# DS_NEW.net
KiCad netlist of a schematic drawn in Altium Designer
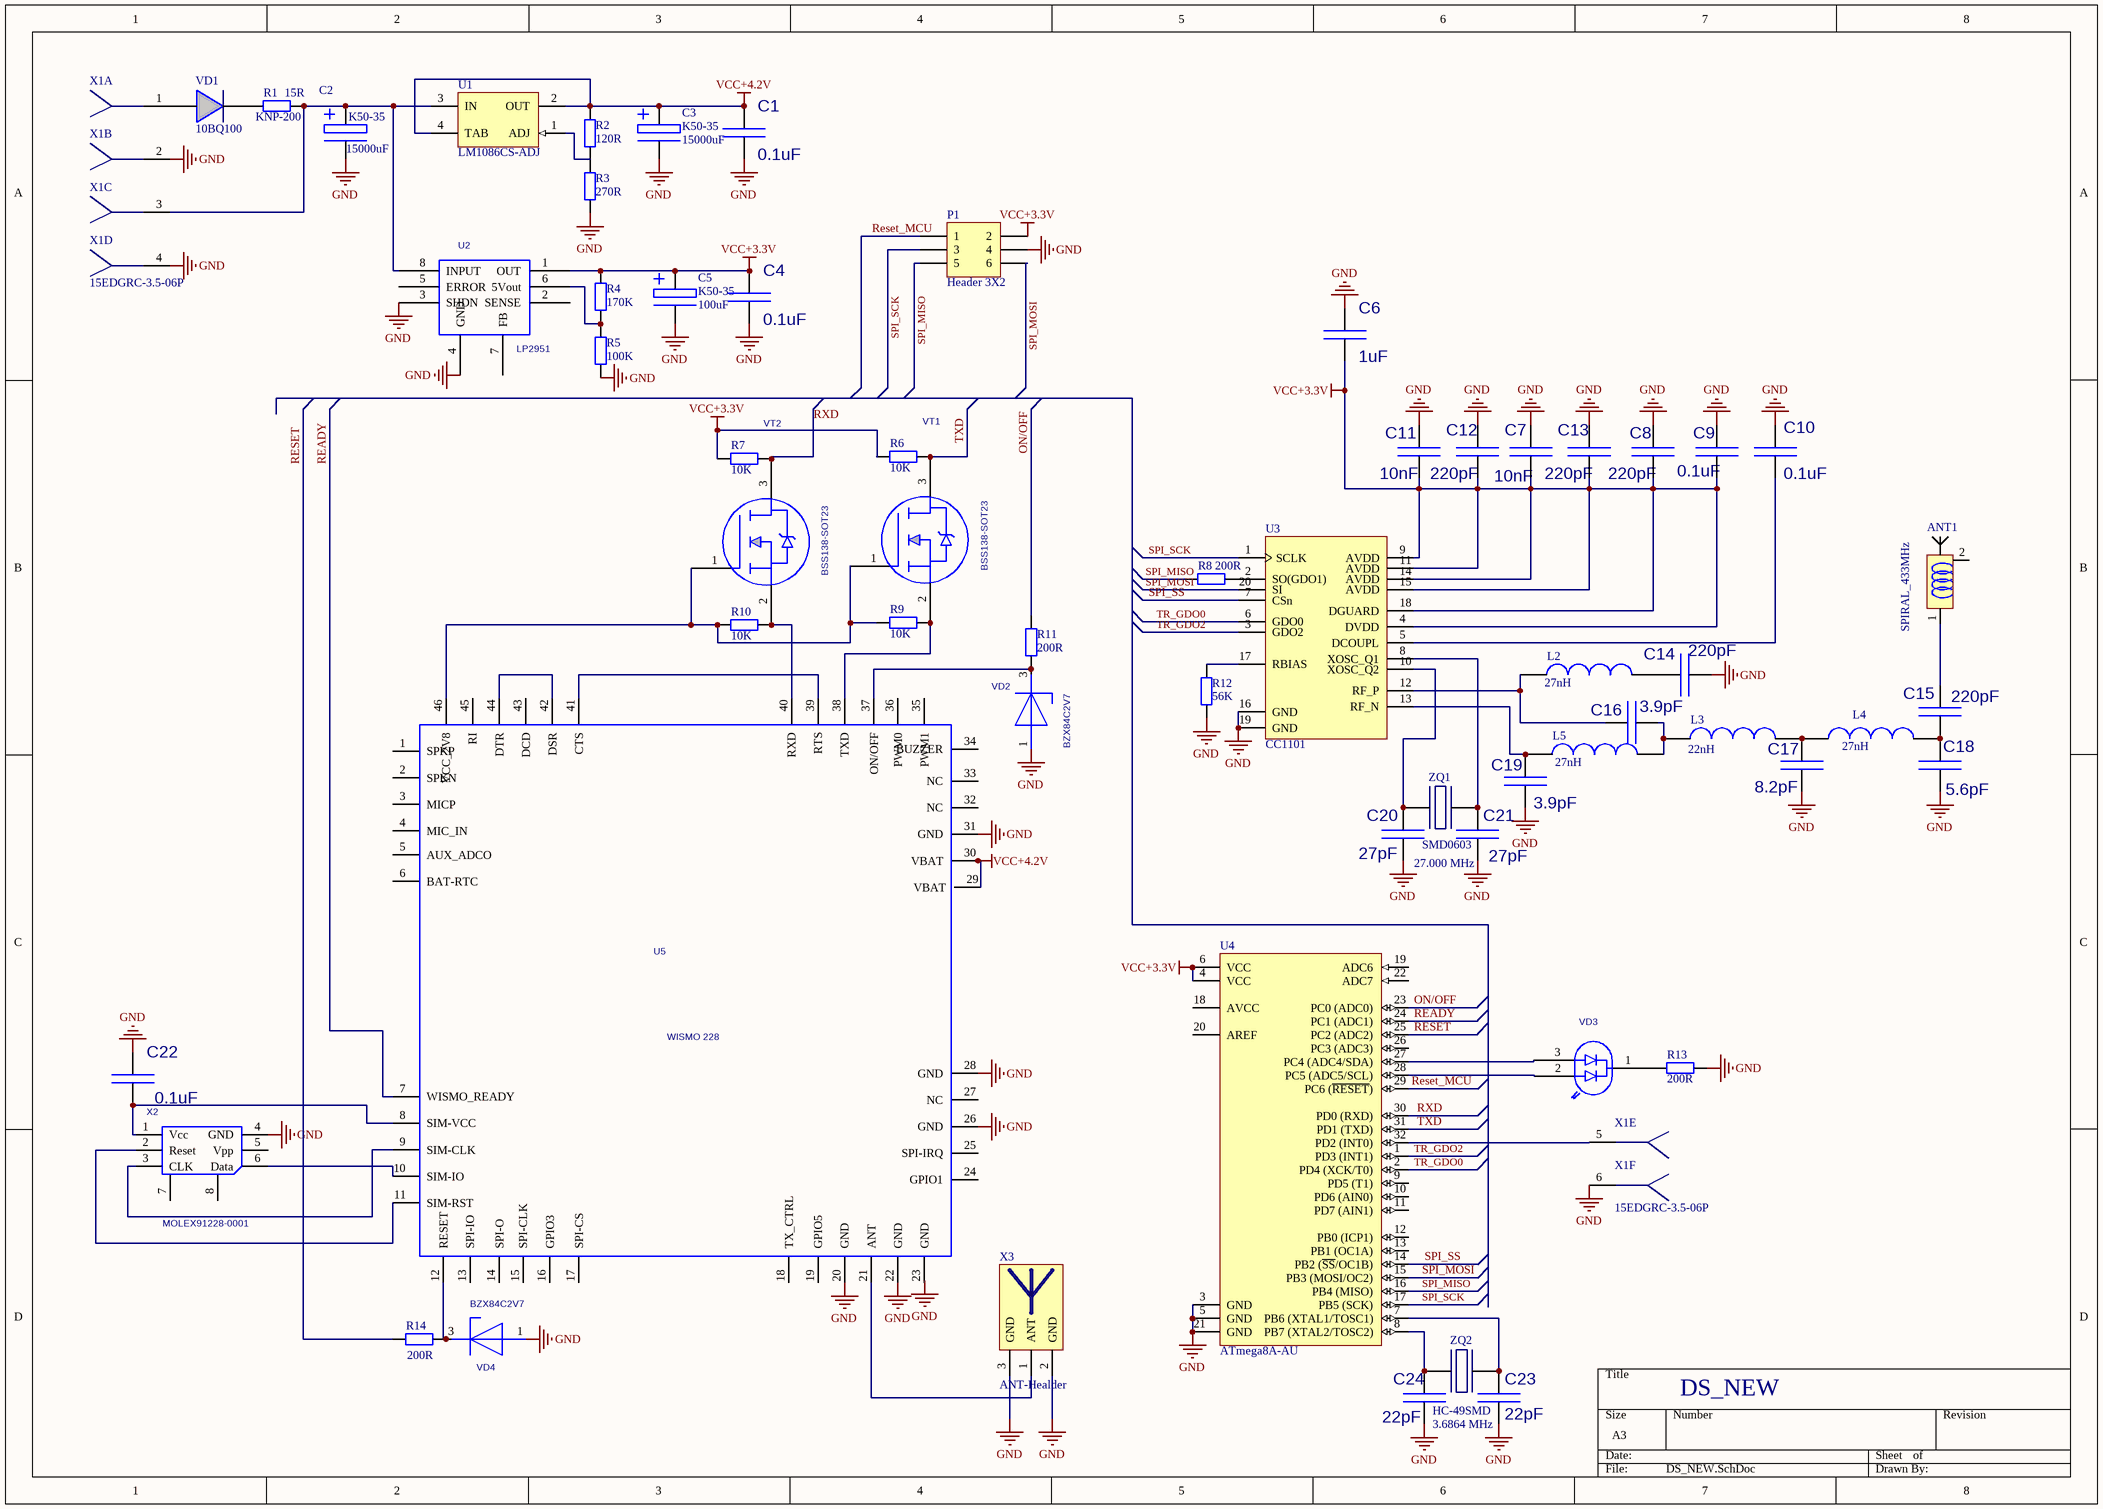
[diagram p0: DS_NEW.SchDoc]

(export (version "E")
  (design (tool "Eeschema 10.0.6"))
  (components
    (comp (ref "ANT1")
      (value "SPIRAL_433MHz")
      (footprint "ANT_433MHz_SPIRAL")
      (libsource (lib "NEW") (part "ANT_433MHz_SPIRAL"))
    )
    (comp (ref "C1")
      (value "0.1uF")
      (footprint "C0805")
      (description "KONDENS_SMD")
      (libsource (lib "NEW") (part "KONDENS_SMD"))
    )
    (comp (ref "C2")
      (value "K50-35")
      (footprint "CAP_POL_D18-Horizontal")
      (fields (field (name "ALTIUM_UNNAMED_1") "15000uF"))
      (libsource (lib "NEW") (part "Capasitor _pol D18"))
    )
    (comp (ref "C3")
      (value "K50-35")
      (footprint "CAP_POL_D18-Horizontal")
      (fields (field (name "ALTIUM_UNNAMED_1") "15000uF"))
      (libsource (lib "NEW") (part "Capasitor _pol D18"))
    )
    (comp (ref "C4")
      (value "0.1uF")
      (footprint "C0805")
      (description "KONDENS_SMD")
      (libsource (lib "NEW") (part "KONDENS_SMD"))
    )
    (comp (ref "C5")
      (value "K50-35")
      (footprint "CAP_POL_D6.3")
      (fields (field (name "ALTIUM_VALUE") "100uF"))
      (libsource (lib "NEW") (part "Capasitor_pol D6.3"))
    )
    (comp (ref "C6")
      (value "1uF")
      (footprint "C0805")
      (description "KONDENS_SMD")
      (libsource (lib "NEW") (part "KONDENS_SMD"))
    )
    (comp (ref "C7")
      (value "10nF")
      (footprint "C0805")
      (description "KONDENS_SMD")
      (libsource (lib "NEW") (part "KONDENS_SMD"))
    )
    (comp (ref "C8")
      (value "220pF")
      (footprint "C0805")
      (description "KONDENS_SMD")
      (libsource (lib "NEW") (part "KONDENS_SMD"))
    )
    (comp (ref "C9")
      (value "0.1uF")
      (footprint "C0805")
      (description "KONDENS_SMD")
      (libsource (lib "NEW") (part "KONDENS_SMD"))
    )
    (comp (ref "C10")
      (value "0.1uF")
      (footprint "C0805")
      (description "KONDENS_SMD")
      (libsource (lib "NEW") (part "KONDENS_SMD"))
    )
    (comp (ref "C11")
      (value "10nF")
      (footprint "C0805")
      (description "KONDENS_SMD")
      (libsource (lib "NEW") (part "KONDENS_SMD"))
    )
    (comp (ref "C12")
      (value "220pF")
      (footprint "C0805")
      (description "KONDENS_SMD")
      (libsource (lib "NEW") (part "KONDENS_SMD"))
    )
    (comp (ref "C13")
      (value "220pF")
      (footprint "C0805")
      (description "KONDENS_SMD")
      (libsource (lib "NEW") (part "KONDENS_SMD"))
    )
    (comp (ref "C14")
      (value "220pF")
      (footprint "C0805")
      (description "KONDENS_SMD")
      (libsource (lib "NEW") (part "KONDENS_SMD"))
    )
    (comp (ref "C15")
      (value "220pF")
      (footprint "C0805")
      (description "KONDENS_SMD")
      (libsource (lib "NEW") (part "KONDENS_SMD"))
    )
    (comp (ref "C16")
      (value "3.9pF")
      (footprint "C0805")
      (description "KONDENS_SMD")
      (libsource (lib "NEW") (part "KONDENS_SMD"))
    )
    (comp (ref "C17")
      (value "8.2pF")
      (footprint "C0805")
      (description "KONDENS_SMD")
      (libsource (lib "NEW") (part "KONDENS_SMD"))
    )
    (comp (ref "C18")
      (value "5.6pF")
      (footprint "C0805")
      (description "KONDENS_SMD")
      (libsource (lib "NEW") (part "KONDENS_SMD"))
    )
    (comp (ref "C19")
      (value "3.9pF")
      (footprint "C0805")
      (description "KONDENS_SMD")
      (libsource (lib "NEW") (part "KONDENS_SMD"))
    )
    (comp (ref "C20")
      (value "27pF")
      (footprint "C0805")
      (description "KONDENS_SMD")
      (libsource (lib "NEW") (part "KONDENS_SMD"))
    )
    (comp (ref "C21")
      (value "27pF")
      (footprint "C0805")
      (description "KONDENS_SMD")
      (libsource (lib "NEW") (part "KONDENS_SMD"))
    )
    (comp (ref "C22")
      (value "0.1uF")
      (footprint "C0805")
      (description "KONDENS_SMD")
      (libsource (lib "NEW") (part "KONDENS_SMD"))
    )
    (comp (ref "C23")
      (value "22pF")
      (footprint "C0805")
      (description "KONDENS_SMD")
      (libsource (lib "NEW") (part "KONDENS_SMD"))
    )
    (comp (ref "C24")
      (value "22pF")
      (footprint "C0805")
      (description "KONDENS_SMD")
      (libsource (lib "NEW") (part "KONDENS_SMD"))
    )
    (comp (ref "L2")
      (value "27nH")
      (footprint "6-0805_M")
      (fields (field (name "Comment") "SMD_0805"))
      (libsource (lib "NEW") (part "Induktor_0805"))
    )
    (comp (ref "L3")
      (value "22nH")
      (footprint "6-0805_M")
      (fields (field (name "Comment") "SMD_0805"))
      (libsource (lib "NEW") (part "Induktor_0805"))
    )
    (comp (ref "L4")
      (value "27nH")
      (footprint "6-0805_M")
      (fields (field (name "Comment") "SMD_0805"))
      (libsource (lib "NEW") (part "Induktor_0805"))
    )
    (comp (ref "L5")
      (value "27nH")
      (footprint "6-0805_M")
      (fields (field (name "Comment") "SMD_0805"))
      (libsource (lib "NEW") (part "Induktor_0805"))
    )
    (comp (ref "P1")
      (value "Header 3X2")
      (footprint "HDR2X3")
      (description "Header, 3-Pin, Dual row")
      (fields (field (name "PUBLISHER") "Altium Limited"))
      (libsource (lib "Miscellaneous Connectors") (part "Header 3X2"))
    )
    (comp (ref "R1")
      (value "KNP-200")
      (footprint "Resistor KNP-200")
      (fields (field (name "ALTIUM_UNNAMED_1") "15R"))
      (libsource (lib "NEW") (part "Resistor 2W"))
    )
    (comp (ref "R2")
      (value "120R")
      (footprint "C0805")
      (description "Resistor")
      (fields (field (name "Comment") "RES"))
      (libsource (lib "") (part "RES_1"))
    )
    (comp (ref "R3")
      (value "270R")
      (footprint "C0805")
      (description "Resistor")
      (fields (field (name "Comment") "RES"))
      (libsource (lib "") (part "RES_1"))
    )
    (comp (ref "R4")
      (value "170K")
      (footprint "C0805")
      (description "Resistor")
      (fields (field (name "Comment") "RES"))
      (libsource (lib "") (part "RES_1"))
    )
    (comp (ref "R5")
      (value "100K")
      (footprint "C0805")
      (description "Resistor")
      (fields (field (name "Comment") "RES"))
      (libsource (lib "") (part "RES_1"))
    )
    (comp (ref "R6")
      (value "10K")
      (footprint "C0805")
      (description "Resistor")
      (fields (field (name "Comment") "RES"))
      (libsource (lib "NEW") (part "RES"))
    )
    (comp (ref "R7")
      (value "10K")
      (footprint "C0805")
      (description "Resistor")
      (fields (field (name "Comment") "RES"))
      (libsource (lib "NEW") (part "RES"))
    )
    (comp (ref "R8")
      (value "200R")
      (footprint "C0805")
      (description "Resistor")
      (fields (field (name "Comment") "RES"))
      (libsource (lib "NEW") (part "RES"))
    )
    (comp (ref "R9")
      (value "10K")
      (footprint "C0805")
      (description "Resistor")
      (fields (field (name "Comment") "RES"))
      (libsource (lib "NEW") (part "RES"))
    )
    (comp (ref "R10")
      (value "10K")
      (footprint "C0805")
      (description "Resistor")
      (fields (field (name "Comment") "RES"))
      (libsource (lib "NEW") (part "RES"))
    )
    (comp (ref "R11")
      (value "200R")
      (footprint "C0805")
      (description "Resistor")
      (fields (field (name "Comment") "RES"))
      (libsource (lib "") (part "RES_1"))
    )
    (comp (ref "R12")
      (value "56K")
      (footprint "C0805")
      (description "Resistor")
      (fields (field (name "Comment") "RES"))
      (libsource (lib "") (part "RES_1"))
    )
    (comp (ref "R13")
      (value "200R")
      (footprint "C0805")
      (description "Resistor")
      (fields (field (name "Comment") "RES"))
      (libsource (lib "NEW") (part "RES"))
    )
    (comp (ref "R14")
      (value "200R")
      (footprint "C0805")
      (description "Resistor")
      (fields (field (name "Comment") "RES"))
      (libsource (lib "NEW") (part "RES"))
    )
    (comp (ref "U1")
      (value "LM1086CS-ADJ")
      (footprint "TS3B_M")
      (description "1.5A Low Dropout Positive Regulators, 3-pin TO-263")
      (fields
        (field (name "MANUFACTURER") "National Semiconductor")
        (field (name "PUBLISHER") "Altium Limited")
      )
      (libsource (lib "NSC LDO") (part "LM1086CS-ADJ"))
    )
    (comp (ref "U2") (value "LP2951") (footprint "SOIC-8") (libsource (lib "NEW") (part "LP2951")))
    (comp (ref "U3") (value "CC1101") (footprint "VQFN20") (libsource (lib "NEW") (part "CC1101")))
    (comp (ref "U4")
      (value "ATmega8A-AU")
      (footprint "32A_N")
      (fields (field (name "PUBLISHER") "Altium Limited"))
      (libsource (lib "Atmel Microcontroller 8-Bit megaAVR") (part "ATmega8A-AU"))
    )
    (comp (ref "U5") (value "WISMO 228") (footprint "WISMO") (libsource (lib "NEW") (part "WISMO 228")))
    (comp (ref "VD1") (value "10BQ100") (footprint "SMB") (libsource (lib "NEW") (part "10BQ100")))
    (comp (ref "VD2") (value "BZX84C2V7") (footprint "SOT23") (libsource (lib "NEW") (part "BZX84C2V7")))
    (comp (ref "VD3")
      (value "LIGHTDIODE2")
      (footprint "LIGHTDIODE2")
      (libsource (lib "NEW") (part "LIGHTDIODE2"))
    )
    (comp (ref "VD4") (value "BZX84C2V7") (footprint "SOT23") (libsource (lib "NEW") (part "BZX84C2V7")))
    (comp (ref "VT1")
      (value "BSS138-SOT23")
      (footprint "SOT23")
      (libsource (lib "NEW") (part "BSS138-SOT23"))
    )
    (comp (ref "VT2")
      (value "BSS138-SOT23")
      (footprint "SOT23")
      (libsource (lib "NEW") (part "BSS138-SOT23"))
    )
    (comp (ref "X1")
      (value "15EDGRC-3.5-06P")
      (footprint "15EDGRC-3.5-06P")
      (libsource (lib "NEW") (part "15EDGRC-3.5-06P"))
    )
    (comp (ref "X2")
      (value "MOLEX91228-0001")
      (footprint "MOLEX91228-0001")
      (libsource (lib "NEW") (part "MOLEX91228-0001"))
    )
    (comp (ref "X3")
      (value "ANT-Healder")
      (footprint "ANT-Healder")
      (libsource (lib "NEW") (part "ANT_HELDER"))
    )
    (comp (ref "ZQ1")
      (value "SMD0603")
      (footprint "Quartz_SMD0603")
      (fields (field (name "ALTIUM_VALUE") "27.000 MHz"))
      (libsource (lib "NEW") (part "Quartz_SMD0603"))
    )
    (comp (ref "ZQ2")
      (value "HC-49SMD")
      (footprint "HC-49SMD")
      (fields (field (name "ALTIUM_VALUE") "3.6864 MHz"))
      (libsource (lib "NEW") (part "HC-49SMD"))
    )
  )
  (nets
    (net (code "1") (name "/ON{slash}OFF") (class "Default")
      (node (ref "R11") (pin "2") (pinfunction "2_2") (pintype "passive"))
      (node (ref "U4") (pin "23") (pinfunction "PC0_(ADC0)_23") (pintype "bidirectional"))
    )
    (net (code "2") (name "/READY") (class "Default")
      (node (ref "U4") (pin "24") (pinfunction "PC1_(ADC1)_24") (pintype "bidirectional"))
      (node (ref "U5") (pin "7") (pinfunction "WISMO_READY_7") (pintype "passive"))
    )
    (net (code "3") (name "/RESET") (class "Default")
      (node (ref "R14") (pin "2") (pinfunction "2_2") (pintype "passive"))
      (node (ref "U4") (pin "25") (pinfunction "PC2_(ADC2)_25") (pintype "bidirectional"))
    )
    (net (code "4") (name "/RXD") (class "Default")
      (node (ref "R7") (pin "1") (pinfunction "1_1") (pintype "passive"))
      (node (ref "U4") (pin "30") (pinfunction "PD0_(RXD)_30") (pintype "bidirectional"))
      (node (ref "VT2") (pin "3") (pinfunction "Drain_3") (pintype "passive"))
    )
    (net (code "5") (name "/Reset_MCU") (class "Default")
      (node (ref "P1") (pin "1") (pinfunction "1_1") (pintype "passive"))
      (node (ref "U4") (pin "29") (pinfunction "PC6_(~{RESET})_29") (pintype "bidirectional"))
    )
    (net (code "6") (name "/SPI_MISO") (class "Default")
      (node (ref "P1") (pin "5") (pinfunction "5_5") (pintype "passive"))
      (node (ref "R8") (pin "2") (pinfunction "2_2") (pintype "passive"))
      (node (ref "U4") (pin "16") (pinfunction "PB4_(MISO)_16") (pintype "bidirectional"))
    )
    (net (code "7") (name "/SPI_MOSI") (class "Default")
      (node (ref "P1") (pin "6") (pinfunction "6_6") (pintype "passive"))
      (node (ref "U3") (pin "20") (pinfunction "SI_20") (pintype "passive"))
      (node (ref "U4") (pin "15") (pinfunction "PB3_(MOSI/OC2)_15") (pintype "bidirectional"))
    )
    (net (code "8") (name "/SPI_SCK") (class "Default")
      (node (ref "P1") (pin "3") (pinfunction "3_3") (pintype "passive"))
      (node (ref "U3") (pin "1") (pinfunction "SCLK_1") (pintype "passive"))
      (node (ref "U4") (pin "17") (pinfunction "PB5_(SCK)_17") (pintype "bidirectional"))
    )
    (net (code "9") (name "/SPI_SS") (class "Default")
      (node (ref "U3") (pin "7") (pinfunction "CSn_7") (pintype "passive"))
      (node (ref "U4") (pin "14") (pinfunction "PB2_(~{SS}/OC1B)_14") (pintype "bidirectional"))
    )
    (net (code "10") (name "/TR_GDO0") (class "Default")
      (node (ref "U3") (pin "6") (pinfunction "GDO0_6") (pintype "passive"))
      (node (ref "U4") (pin "2") (pinfunction "PD4_(XCK/T0)_2") (pintype "bidirectional"))
    )
    (net (code "11") (name "/TR_GDO2") (class "Default")
      (node (ref "U3") (pin "3") (pinfunction "GDO2_3") (pintype "passive"))
      (node (ref "U4") (pin "1") (pinfunction "PD3_(INT1)_1") (pintype "bidirectional"))
    )
    (net (code "12") (name "/TXD") (class "Default")
      (node (ref "R6") (pin "1") (pinfunction "1_1") (pintype "passive"))
      (node (ref "U4") (pin "31") (pinfunction "PD1_(TXD)_31") (pintype "bidirectional"))
      (node (ref "VT1") (pin "3") (pinfunction "Drain_3") (pintype "passive"))
    )
    (net (code "13") (name "GND") (class "Default")
      (node (ref "C1") (pin "2") (pinfunction "B_2") (pintype "passive"))
      (node (ref "C10") (pin "1") (pinfunction "A_1") (pintype "passive"))
      (node (ref "C11") (pin "1") (pinfunction "A_1") (pintype "passive"))
      (node (ref "C12") (pin "1") (pinfunction "A_1") (pintype "passive"))
      (node (ref "C13") (pin "1") (pinfunction "A_1") (pintype "passive"))
      (node (ref "C14") (pin "2") (pinfunction "B_2") (pintype "passive"))
      (node (ref "C17") (pin "2") (pinfunction "B_2") (pintype "passive"))
      (node (ref "C18") (pin "2") (pinfunction "B_2") (pintype "passive"))
      (node (ref "C19") (pin "2") (pinfunction "B_2") (pintype "passive"))
      (node (ref "C2") (pin "2") (pinfunction "MINUS_2") (pintype "passive"))
      (node (ref "C20") (pin "2") (pinfunction "B_2") (pintype "passive"))
      (node (ref "C21") (pin "2") (pinfunction "B_2") (pintype "passive"))
      (node (ref "C22") (pin "1") (pinfunction "A_1") (pintype "passive"))
      (node (ref "C23") (pin "2") (pinfunction "B_2") (pintype "passive"))
      (node (ref "C24") (pin "2") (pinfunction "B_2") (pintype "passive"))
      (node (ref "C3") (pin "2") (pinfunction "MINUS_2") (pintype "passive"))
      (node (ref "C4") (pin "2") (pinfunction "B_2") (pintype "passive"))
      (node (ref "C5") (pin "2") (pinfunction "MINUS_2") (pintype "passive"))
      (node (ref "C6") (pin "1") (pinfunction "A_1") (pintype "passive"))
      (node (ref "C7") (pin "1") (pinfunction "A_1") (pintype "passive"))
      (node (ref "C8") (pin "1") (pinfunction "A_1") (pintype "passive"))
      (node (ref "C9") (pin "1") (pinfunction "A_1") (pintype "passive"))
      (node (ref "P1") (pin "4") (pinfunction "4_4") (pintype "passive"))
      (node (ref "R12") (pin "1") (pinfunction "1_1") (pintype "passive"))
      (node (ref "R13") (pin "1") (pinfunction "1_1") (pintype "passive"))
      (node (ref "R3") (pin "1") (pinfunction "1_1") (pintype "passive"))
      (node (ref "R5") (pin "1") (pinfunction "1_1") (pintype "passive"))
      (node (ref "U2") (pin "3") (pinfunction "SHDN_3") (pintype "passive"))
      (node (ref "U2") (pin "4") (pinfunction "GND_4") (pintype "passive"))
      (node (ref "U3") (pin "16") (pinfunction "GND_16") (pintype "passive"))
      (node (ref "U3") (pin "19") (pinfunction "GND_19") (pintype "passive"))
      (node (ref "U4") (pin "21") (pinfunction "GND_21") (pintype "power_in"))
      (node (ref "U4") (pin "3") (pinfunction "GND_3") (pintype "power_in"))
      (node (ref "U4") (pin "5") (pinfunction "GND_5") (pintype "power_in"))
      (node (ref "U5") (pin "20") (pinfunction "GND_20") (pintype "passive"))
      (node (ref "U5") (pin "22") (pinfunction "GND_22") (pintype "passive"))
      (node (ref "U5") (pin "26") (pinfunction "GND_26") (pintype "passive"))
      (node (ref "U5") (pin "28") (pinfunction "GND_28") (pintype "passive"))
      (node (ref "U5") (pin "31") (pinfunction "GND_31") (pintype "passive"))
      (node (ref "VD2") (pin "1") (pinfunction "1_1") (pintype "passive"))
      (node (ref "VD4") (pin "1") (pinfunction "1_1") (pintype "passive"))
      (node (ref "X1") (pin "2") (pinfunction "2_2") (pintype "passive"))
      (node (ref "X1") (pin "4") (pinfunction "4_4") (pintype "passive"))
      (node (ref "X1") (pin "6") (pinfunction "6_6") (pintype "passive"))
      (node (ref "X2") (pin "4") (pinfunction "GND_4") (pintype "passive"))
      (node (ref "X3") (pin "2") (pinfunction "GND_2") (pintype "passive"))
      (node (ref "X3") (pin "3") (pinfunction "GND_3") (pintype "passive"))
    )
    (net (code "14") (name "Net-(C2-PLUS)") (class "Default")
      (node (ref "C2") (pin "1") (pinfunction "PLUS_1") (pintype "passive"))
      (node (ref "R1") (pin "2") (pinfunction "2_2") (pintype "passive"))
      (node (ref "U1") (pin "3") (pinfunction "IN_3") (pintype "power_in"))
      (node (ref "U2") (pin "8") (pinfunction "INPUT_8") (pintype "passive"))
      (node (ref "X1") (pin "3") (pinfunction "3_3") (pintype "passive"))
    )
    (net (code "15") (name "Net-(C10-B)") (class "Default")
      (node (ref "C10") (pin "2") (pinfunction "B_2") (pintype "passive"))
      (node (ref "U3") (pin "5") (pinfunction "DCOUPL_5") (pintype "passive"))
    )
    (net (code "16") (name "Net-(C14-A)") (class "Default")
      (node (ref "C14") (pin "1") (pinfunction "A_1") (pintype "passive"))
      (node (ref "L2") (pin "2") (pinfunction "2_2") (pintype "passive"))
    )
    (net (code "17") (name "Net-(C15-A)") (class "Default")
      (node (ref "ANT1") (pin "1") (pinfunction "1_1") (pintype "passive"))
      (node (ref "C15") (pin "1") (pinfunction "A_1") (pintype "passive"))
    )
    (net (code "18") (name "Net-(C15-B)") (class "Default")
      (node (ref "C15") (pin "2") (pinfunction "B_2") (pintype "passive"))
      (node (ref "C18") (pin "1") (pinfunction "A_1") (pintype "passive"))
      (node (ref "L4") (pin "2") (pinfunction "2_2") (pintype "passive"))
    )
    (net (code "19") (name "Net-(C16-A)") (class "Default")
      (node (ref "C16") (pin "1") (pinfunction "A_1") (pintype "passive"))
      (node (ref "L2") (pin "1") (pinfunction "1_1") (pintype "passive"))
      (node (ref "U3") (pin "12") (pinfunction "RF_P_12") (pintype "passive"))
    )
    (net (code "20") (name "Net-(C16-B)") (class "Default")
      (node (ref "C16") (pin "2") (pinfunction "B_2") (pintype "passive"))
      (node (ref "L3") (pin "1") (pinfunction "1_1") (pintype "passive"))
      (node (ref "L5") (pin "2") (pinfunction "2_2") (pintype "passive"))
    )
    (net (code "21") (name "Net-(C17-A)") (class "Default")
      (node (ref "C17") (pin "1") (pinfunction "A_1") (pintype "passive"))
      (node (ref "L3") (pin "2") (pinfunction "2_2") (pintype "passive"))
      (node (ref "L4") (pin "1") (pinfunction "1_1") (pintype "passive"))
    )
    (net (code "22") (name "Net-(C19-A)") (class "Default")
      (node (ref "C19") (pin "1") (pinfunction "A_1") (pintype "passive"))
      (node (ref "L5") (pin "1") (pinfunction "1_1") (pintype "passive"))
      (node (ref "U3") (pin "13") (pinfunction "RF_N_13") (pintype "passive"))
    )
    (net (code "23") (name "Net-(C20-A)") (class "Default")
      (node (ref "C20") (pin "1") (pinfunction "A_1") (pintype "passive"))
      (node (ref "U3") (pin "10") (pinfunction "XOSC_Q2_10") (pintype "passive"))
      (node (ref "ZQ1") (pin "3") (pinfunction "3_3") (pintype "passive"))
    )
    (net (code "24") (name "Net-(C21-A)") (class "Default")
      (node (ref "C21") (pin "1") (pinfunction "A_1") (pintype "passive"))
      (node (ref "U3") (pin "8") (pinfunction "XOSC_Q1_8") (pintype "passive"))
      (node (ref "ZQ1") (pin "1") (pinfunction "1_1") (pintype "passive"))
    )
    (net (code "25") (name "Net-(C22-B)") (class "Default")
      (node (ref "C22") (pin "2") (pinfunction "B_2") (pintype "passive"))
      (node (ref "U5") (pin "8") (pinfunction "SIM-VCC_8") (pintype "passive"))
      (node (ref "X2") (pin "1") (pinfunction "Vcc_1") (pintype "passive"))
    )
    (net (code "26") (name "Net-(C23-A)") (class "Default")
      (node (ref "C23") (pin "1") (pinfunction "A_1") (pintype "passive"))
      (node (ref "U4") (pin "7") (pinfunction "PB6_(XTAL1/TOSC1)_7") (pintype "bidirectional"))
      (node (ref "ZQ2") (pin "1") (pinfunction "1_1") (pintype "passive"))
    )
    (net (code "27") (name "Net-(C24-A)") (class "Default")
      (node (ref "C24") (pin "1") (pinfunction "A_1") (pintype "passive"))
      (node (ref "U4") (pin "8") (pinfunction "PB7_(XTAL2/TOSC2)_8") (pintype "bidirectional"))
      (node (ref "ZQ2") (pin "2") (pinfunction "2_2") (pintype "passive"))
    )
    (net (code "28") (name "Net-(R1-Pad1)") (class "Default")
      (node (ref "R1") (pin "1") (pinfunction "1_1") (pintype "passive"))
      (node (ref "VD1") (pin "1") (pinfunction "1_1") (pintype "passive"))
    )
    (net (code "29") (name "Net-(R13-Pad2)") (class "Default")
      (node (ref "R13") (pin "2") (pinfunction "2_2") (pintype "passive"))
      (node (ref "VD3") (pin "1") (pintype "passive"))
    )
    (net (code "30") (name "Net-(U1-ADJ)") (class "Default")
      (node (ref "R3") (pin "2") (pinfunction "2_2") (pintype "passive"))
      (node (ref "U1") (pin "1") (pinfunction "ADJ_1") (pintype "input"))
    )
    (net (code "31") (name "Net-(U2-5Vout)") (class "Default")
      (node (ref "R4") (pin "1") (pinfunction "1_1") (pintype "passive"))
      (node (ref "R5") (pin "2") (pinfunction "2_2") (pintype "passive"))
      (node (ref "U2") (pin "6") (pinfunction "5Vout_6") (pintype "passive"))
    )
    (net (code "32") (name "Net-(U3-RBIAS)") (class "Default")
      (node (ref "R12") (pin "2") (pinfunction "2_2") (pintype "passive"))
      (node (ref "U3") (pin "17") (pinfunction "RBIAS_17") (pintype "passive"))
    )
    (net (code "33") (name "Net-(U3-SO(GDO1))") (class "Default")
      (node (ref "R8") (pin "1") (pinfunction "1_1") (pintype "passive"))
      (node (ref "U3") (pin "2") (pinfunction "SO(GDO1)_2") (pintype "passive"))
    )
    (net (code "34") (name "Net-(U4-PC4_(ADC4{slash}SDA))") (class "Default")
      (node (ref "U4") (pin "27") (pinfunction "PC4_(ADC4/SDA)_27") (pintype "bidirectional"))
      (node (ref "VD3") (pin "3") (pintype "passive"))
    )
    (net (code "35") (name "Net-(U4-PC5_(ADC5{slash}SCL))") (class "Default")
      (node (ref "U4") (pin "28") (pinfunction "PC5_(ADC5/SCL)_28") (pintype "bidirectional"))
      (node (ref "VD3") (pin "2") (pintype "passive"))
    )
    (net (code "36") (name "Net-(U4-PD2_(INT0))") (class "Default")
      (node (ref "U4") (pin "32") (pinfunction "PD2_(INT0)_32") (pintype "bidirectional"))
      (node (ref "X1") (pin "5") (pinfunction "5_5") (pintype "passive"))
    )
    (net (code "37") (name "Net-(U5-ANT)") (class "Default")
      (node (ref "U5") (pin "21") (pinfunction "ANT_21") (pintype "passive"))
      (node (ref "X3") (pin "1") (pinfunction "ANT_1") (pintype "passive"))
    )
    (net (code "38") (name "Net-(U5-CTS)") (class "Default")
      (node (ref "U5") (pin "39") (pinfunction "RTS_39") (pintype "passive"))
      (node (ref "U5") (pin "41") (pinfunction "CTS_41") (pintype "passive"))
    )
    (net (code "39") (name "Net-(U5-DSR)") (class "Default")
      (node (ref "U5") (pin "42") (pinfunction "DSR_42") (pintype "passive"))
      (node (ref "U5") (pin "44") (pinfunction "DTR_44") (pintype "passive"))
    )
    (net (code "40") (name "Net-(U5-ON{slash}OFF)") (class "Default")
      (node (ref "R11") (pin "1") (pinfunction "1_1") (pintype "passive"))
      (node (ref "U5") (pin "37") (pinfunction "ON/OFF_37") (pintype "passive"))
      (node (ref "VD2") (pin "3") (pinfunction "2_3") (pintype "passive"))
    )
    (net (code "41") (name "Net-(U5-RESET)") (class "Default")
      (node (ref "R14") (pin "1") (pinfunction "1_1") (pintype "passive"))
      (node (ref "U5") (pin "12") (pinfunction "RESET_12") (pintype "passive"))
      (node (ref "VD4") (pin "3") (pinfunction "2_3") (pintype "passive"))
    )
    (net (code "42") (name "Net-(U5-RXD)") (class "Default")
      (node (ref "R10") (pin "1") (pinfunction "1_1") (pintype "passive"))
      (node (ref "U5") (pin "40") (pinfunction "RXD_40") (pintype "passive"))
      (node (ref "VT2") (pin "2") (pinfunction "Source_2") (pintype "passive"))
    )
    (net (code "43") (name "Net-(U5-SIM-CLK)") (class "Default")
      (node (ref "U5") (pin "9") (pinfunction "SIM-CLK_9") (pintype "passive"))
      (node (ref "X2") (pin "3") (pinfunction "CLK_3") (pintype "passive"))
    )
    (net (code "44") (name "Net-(U5-SIM-IO)") (class "Default")
      (node (ref "U5") (pin "10") (pinfunction "SIM-IO_10") (pintype "passive"))
      (node (ref "X2") (pin "6") (pinfunction "Data_6") (pintype "passive"))
    )
    (net (code "45") (name "Net-(U5-SIM-RST)") (class "Default")
      (node (ref "U5") (pin "11") (pinfunction "SIM-RST_11") (pintype "passive"))
      (node (ref "X2") (pin "2") (pinfunction "Reset_2") (pintype "passive"))
    )
    (net (code "46") (name "Net-(U5-TXD)") (class "Default")
      (node (ref "R9") (pin "1") (pinfunction "1_1") (pintype "passive"))
      (node (ref "U5") (pin "38") (pinfunction "TXD_38") (pintype "passive"))
      (node (ref "VT1") (pin "2") (pinfunction "Source_2") (pintype "passive"))
    )
    (net (code "47") (name "Net-(U5-VCC_2V8)") (class "Default")
      (node (ref "R10") (pin "2") (pinfunction "2_2") (pintype "passive"))
      (node (ref "R9") (pin "2") (pinfunction "2_2") (pintype "passive"))
      (node (ref "U5") (pin "46") (pinfunction "VCC_2V8_46") (pintype "passive"))
      (node (ref "VT1") (pin "1") (pinfunction "Gate_1") (pintype "passive"))
      (node (ref "VT2") (pin "1") (pinfunction "Gate_1") (pintype "passive"))
    )
    (net (code "48") (name "Net-(VD1-Pad2)") (class "Default")
      (node (ref "VD1") (pin "2") (pinfunction "2_2") (pintype "passive"))
      (node (ref "X1") (pin "1") (pinfunction "1_1") (pintype "passive"))
    )
    (net (code "49") (name "VCC+3.3V") (class "Default")
      (node (ref "C11") (pin "2") (pinfunction "B_2") (pintype "passive"))
      (node (ref "C12") (pin "2") (pinfunction "B_2") (pintype "passive"))
      (node (ref "C13") (pin "2") (pinfunction "B_2") (pintype "passive"))
      (node (ref "C4") (pin "1") (pinfunction "A_1") (pintype "passive"))
      (node (ref "C5") (pin "1") (pinfunction "PLUS_1") (pintype "passive"))
      (node (ref "C6") (pin "2") (pinfunction "B_2") (pintype "passive"))
      (node (ref "C7") (pin "2") (pinfunction "B_2") (pintype "passive"))
      (node (ref "C8") (pin "2") (pinfunction "B_2") (pintype "passive"))
      (node (ref "C9") (pin "2") (pinfunction "B_2") (pintype "passive"))
      (node (ref "P1") (pin "2") (pinfunction "2_2") (pintype "passive"))
      (node (ref "R4") (pin "2") (pinfunction "2_2") (pintype "passive"))
      (node (ref "R6") (pin "2") (pinfunction "2_2") (pintype "passive"))
      (node (ref "R7") (pin "2") (pinfunction "2_2") (pintype "passive"))
      (node (ref "U2") (pin "1") (pinfunction "OUT_1") (pintype "passive"))
      (node (ref "U3") (pin "11") (pinfunction "AVDD_11") (pintype "passive"))
      (node (ref "U3") (pin "14") (pinfunction "AVDD_14") (pintype "passive"))
      (node (ref "U3") (pin "15") (pinfunction "AVDD_15") (pintype "passive"))
      (node (ref "U3") (pin "18") (pinfunction "DGUARD_18") (pintype "passive"))
      (node (ref "U3") (pin "4") (pinfunction "DVDD_4") (pintype "passive"))
      (node (ref "U3") (pin "9") (pinfunction "AVDD_9") (pintype "passive"))
      (node (ref "U4") (pin "4") (pinfunction "VCC_4") (pintype "power_in"))
      (node (ref "U4") (pin "6") (pinfunction "VCC_6") (pintype "power_in"))
    )
    (net (code "50") (name "VCC+4.2V") (class "Default")
      (node (ref "C1") (pin "1") (pinfunction "A_1") (pintype "passive"))
      (node (ref "C3") (pin "1") (pinfunction "PLUS_1") (pintype "passive"))
      (node (ref "R2") (pin "2") (pinfunction "2_2") (pintype "passive"))
      (node (ref "U1") (pin "2") (pinfunction "OUT_2") (pintype "power_in"))
      (node (ref "U1") (pin "4") (pinfunction "TAB_4") (pintype "power_in"))
      (node (ref "U5") (pin "29") (pinfunction "VBAT_29") (pintype "passive"))
      (node (ref "U5") (pin "30") (pinfunction "VBAT_30") (pintype "passive"))
    )
    (net (code "51") (name "unconnected-(ANT1-Pad2)") (class "Default")
      (node (ref "ANT1") (pin "2") (pinfunction "2_2") (pintype "passive"))
    )
    (net (code "52") (name "unconnected-(R2-Pad1)") (class "Default")
      (node (ref "R2") (pin "1") (pinfunction "1_1") (pintype "passive"))
    )
    (net (code "53") (name "unconnected-(U2-ERROR-Pad5)") (class "Default")
      (node (ref "U2") (pin "5") (pinfunction "ERROR_5") (pintype "passive"))
    )
    (net (code "54") (name "unconnected-(U2-FB-Pad7)") (class "Default")
      (node (ref "U2") (pin "7") (pinfunction "FB_7") (pintype "passive"))
    )
    (net (code "55") (name "unconnected-(U2-SENSE-Pad2)") (class "Default")
      (node (ref "U2") (pin "2") (pinfunction "SENSE_2") (pintype "passive"))
    )
    (net (code "56") (name "unconnected-(U4-ADC6-Pad19)") (class "Default")
      (node (ref "U4") (pin "19") (pinfunction "ADC6_19") (pintype "input"))
    )
    (net (code "57") (name "unconnected-(U4-ADC7-Pad22)") (class "Default")
      (node (ref "U4") (pin "22") (pinfunction "ADC7_22") (pintype "input"))
    )
    (net (code "58") (name "unconnected-(U4-AREF-Pad20)") (class "Default")
      (node (ref "U4") (pin "20") (pinfunction "AREF_20") (pintype "power_in"))
    )
    (net (code "59") (name "unconnected-(U4-AVCC-Pad18)") (class "Default")
      (node (ref "U4") (pin "18") (pinfunction "AVCC_18") (pintype "power_in"))
    )
    (net (code "60") (name "unconnected-(U4-PB0_(ICP1)-Pad12)") (class "Default")
      (node (ref "U4") (pin "12") (pinfunction "PB0_(ICP1)_12") (pintype "bidirectional"))
    )
    (net (code "61") (name "unconnected-(U4-PB1_(OC1A)-Pad13)") (class "Default")
      (node (ref "U4") (pin "13") (pinfunction "PB1_(OC1A)_13") (pintype "bidirectional"))
    )
    (net (code "62") (name "unconnected-(U4-PC3_(ADC3)-Pad26)") (class "Default")
      (node (ref "U4") (pin "26") (pinfunction "PC3_(ADC3)_26") (pintype "bidirectional"))
    )
    (net (code "63") (name "unconnected-(U4-PD5_(T1)-Pad9)") (class "Default")
      (node (ref "U4") (pin "9") (pinfunction "PD5_(T1)_9") (pintype "bidirectional"))
    )
    (net (code "64") (name "unconnected-(U4-PD6_(AIN0)-Pad10)") (class "Default")
      (node (ref "U4") (pin "10") (pinfunction "PD6_(AIN0)_10") (pintype "bidirectional"))
    )
    (net (code "65") (name "unconnected-(U4-PD7_(AIN1)-Pad11)") (class "Default")
      (node (ref "U4") (pin "11") (pinfunction "PD7_(AIN1)_11") (pintype "bidirectional"))
    )
    (net (code "66") (name "unconnected-(U5-AUX_ADCO-Pad5)") (class "Default")
      (node (ref "U5") (pin "5") (pinfunction "AUX_ADCO_5") (pintype "passive"))
    )
    (net (code "67") (name "unconnected-(U5-BAT-RTC-Pad6)") (class "Default")
      (node (ref "U5") (pin "6") (pinfunction "BAT-RTC_6") (pintype "passive"))
    )
    (net (code "68") (name "unconnected-(U5-BUZZER-Pad34)") (class "Default")
      (node (ref "U5") (pin "34") (pinfunction "BUZZER_34") (pintype "passive"))
    )
    (net (code "69") (name "unconnected-(U5-DCD-Pad43)") (class "Default")
      (node (ref "U5") (pin "43") (pinfunction "DCD_43") (pintype "passive"))
    )
    (net (code "70") (name "unconnected-(U5-GND-Pad23)") (class "Default")
      (node (ref "U5") (pin "23") (pinfunction "GND_23") (pintype "passive"))
    )
    (net (code "71") (name "unconnected-(U5-GPIO1-Pad24)") (class "Default")
      (node (ref "U5") (pin "24") (pinfunction "GPIO1_24") (pintype "passive"))
    )
    (net (code "72") (name "unconnected-(U5-GPIO3-Pad16)") (class "Default")
      (node (ref "U5") (pin "16") (pinfunction "GPIO3_16") (pintype "passive"))
    )
    (net (code "73") (name "unconnected-(U5-GPIO5-Pad19)") (class "Default")
      (node (ref "U5") (pin "19") (pinfunction "GPIO5_19") (pintype "passive"))
    )
    (net (code "74") (name "unconnected-(U5-MICP-Pad3)") (class "Default")
      (node (ref "U5") (pin "3") (pinfunction "MICP_3") (pintype "passive"))
    )
    (net (code "75") (name "unconnected-(U5-MIC_IN-Pad4)") (class "Default")
      (node (ref "U5") (pin "4") (pinfunction "MIC_IN_4") (pintype "passive"))
    )
    (net (code "76") (name "unconnected-(U5-NC-Pad27)") (class "Default")
      (node (ref "U5") (pin "27") (pinfunction "NC_27") (pintype "passive"))
    )
    (net (code "77") (name "unconnected-(U5-NC-Pad32)") (class "Default")
      (node (ref "U5") (pin "32") (pinfunction "NC_32") (pintype "passive"))
    )
    (net (code "78") (name "unconnected-(U5-NC-Pad33)") (class "Default")
      (node (ref "U5") (pin "33") (pinfunction "NC_33") (pintype "passive"))
    )
    (net (code "79") (name "unconnected-(U5-PWM0-Pad36)") (class "Default")
      (node (ref "U5") (pin "36") (pinfunction "PWM0_36") (pintype "passive"))
    )
    (net (code "80") (name "unconnected-(U5-PWM1-Pad35)") (class "Default")
      (node (ref "U5") (pin "35") (pinfunction "PWM1_35") (pintype "passive"))
    )
    (net (code "81") (name "unconnected-(U5-RI-Pad45)") (class "Default")
      (node (ref "U5") (pin "45") (pinfunction "RI_45") (pintype "passive"))
    )
    (net (code "82") (name "unconnected-(U5-SPI-CLK-Pad15)") (class "Default")
      (node (ref "U5") (pin "15") (pinfunction "SPI-CLK_15") (pintype "passive"))
    )
    (net (code "83") (name "unconnected-(U5-SPI-CS-Pad17)") (class "Default")
      (node (ref "U5") (pin "17") (pinfunction "SPI-CS_17") (pintype "passive"))
    )
    (net (code "84") (name "unconnected-(U5-SPI-IO-Pad13)") (class "Default")
      (node (ref "U5") (pin "13") (pinfunction "SPI-IO_13") (pintype "passive"))
    )
    (net (code "85") (name "unconnected-(U5-SPI-IRQ-Pad25)") (class "Default")
      (node (ref "U5") (pin "25") (pinfunction "SPI-IRQ_25") (pintype "passive"))
    )
    (net (code "86") (name "unconnected-(U5-SPI-O-Pad14)") (class "Default")
      (node (ref "U5") (pin "14") (pinfunction "SPI-O_14") (pintype "passive"))
    )
    (net (code "87") (name "unconnected-(U5-SPKN-Pad2)") (class "Default")
      (node (ref "U5") (pin "2") (pinfunction "SPKN_2") (pintype "passive"))
    )
    (net (code "88") (name "unconnected-(U5-SPKP-Pad1)") (class "Default")
      (node (ref "U5") (pin "1") (pinfunction "SPKP_1") (pintype "passive"))
    )
    (net (code "89") (name "unconnected-(U5-TX_CTRL-Pad18)") (class "Default")
      (node (ref "U5") (pin "18") (pinfunction "TX_CTRL_18") (pintype "passive"))
    )
    (net (code "90") (name "unconnected-(VD2-Pad2)") (class "Default")
      (node (ref "VD2") (pin "2") (pintype "passive"))
    )
    (net (code "91") (name "unconnected-(VD4-Pad2)") (class "Default")
      (node (ref "VD4") (pin "2") (pintype "passive"))
    )
    (net (code "92") (name "unconnected-(X2-0-Pad7)") (class "Default")
      (node (ref "X2") (pin "7") (pinfunction "0_7") (pintype "passive"))
    )
    (net (code "93") (name "unconnected-(X2-1-Pad8)") (class "Default")
      (node (ref "X2") (pin "8") (pinfunction "1_8") (pintype "passive"))
    )
    (net (code "94") (name "unconnected-(X2-Vpp-Pad5)") (class "Default")
      (node (ref "X2") (pin "5") (pinfunction "Vpp_5") (pintype "passive"))
    )
  )
)
